# Sense_LDC1612.net
KiCad netlist of a schematic drawn in Altium Designer
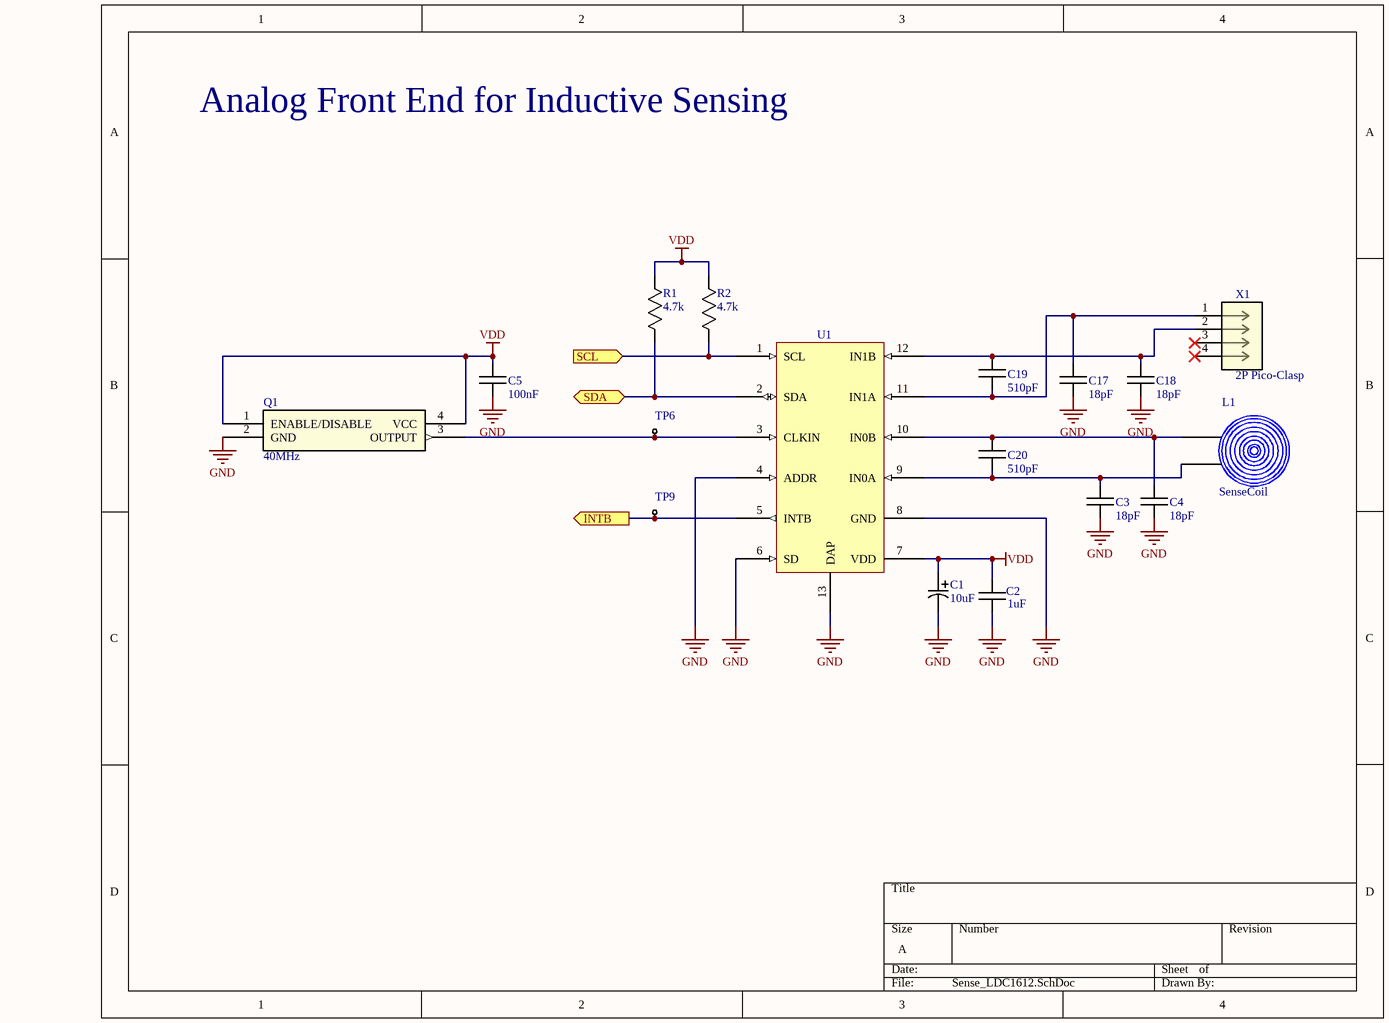
[diagram p0: Sense_LDC1612.SchDoc]

(export (version "E")
  (design (tool "Eeschema 10.0.6"))
  (components
    (comp (ref "C1")
      (value "10uF")
      (footprint "CAP1206_TAJA")
      (description "Cap Tant Solid 10uF 16V A CASE 10%( 3.2 X 1.6 X 1.6mm) Inward L SMD 3216-18 3 Ohm 125C T/R")
      (fields
        (field (name "MANUFACTURER_PART_NUMBER") "TAJA106K016RNJ")
        (field (name "MANUFACTURER") "Kyocera AVX")
        (field (name "COPYRIGHT") "Copyright (C) 2023 Ultra Librarian. All rights reserved.")
      )
      (libsource (lib "Schlib1") (part "TAJA106K016RNJ"))
    )
    (comp (ref "C2")
      (value "1uF")
      (footprint "CAP0805")
      (description "Multilayer Ceramic Capacitor, 1 uF, 50 V, ± 10%, X7R, 0805 [2012 Metric]")
      (fields
        (field (name "MANUFACTURER") "Samsung")
        (field (name "MANUFACTURER PART NUMBER") "CL21B105KBFNNNE")
      )
      (libsource (lib "Schlib1") (part "CL21B105KBFNNNE"))
    )
    (comp (ref "C3")
      (value "18pF")
      (footprint "CAP0805")
      (description "0805 18 pF 50 V ±5 % Tolerance C0G/NP0 SMT Multilayer Ceramic Chip Capacitor")
      (fields
        (field (name "MANUFACTURER") "Vishay")
        (field (name "MANUFACTURER PART NUMBER") "VJ0805A180JXACW1BC")
      )
      (libsource (lib "Schlib1") (part "VJ0805A180JXACW1BC"))
    )
    (comp (ref "C4")
      (value "18pF")
      (footprint "CAP0805")
      (description "0805 18 pF 50 V ±5 % Tolerance C0G/NP0 SMT Multilayer Ceramic Chip Capacitor")
      (fields
        (field (name "MANUFACTURER") "Vishay")
        (field (name "MANUFACTURER PART NUMBER") "VJ0805A180JXACW1BC")
      )
      (libsource (lib "Schlib1") (part "VJ0805A180JXACW1BC"))
    )
    (comp (ref "C5")
      (value "100nF")
      (footprint "CAP0805")
      (description "Multilayer Ceramic Capacitor, 0.1 uF, 50 V, ± 10%, X7R, 0805 [2012 Metric]")
      (fields
        (field (name "MANUFACTURER") "Yageo")
        (field (name "MANUFACTURER PART NUMBER") "CC0805KRX7R9BB104")
      )
      (libsource (lib "Schlib1") (part "CC0805KRX7R9BB104"))
    )
    (comp (ref "C17")
      (value "18pF")
      (footprint "CAP0805")
      (description "0805 18 pF 50 V ±5 % Tolerance C0G/NP0 SMT Multilayer Ceramic Chip Capacitor")
      (fields
        (field (name "MANUFACTURER") "Vishay")
        (field (name "MANUFACTURER PART NUMBER") "VJ0805A180JXACW1BC")
      )
      (libsource (lib "Schlib1") (part "VJ0805A180JXACW1BC"))
    )
    (comp (ref "C18")
      (value "18pF")
      (footprint "CAP0805")
      (description "0805 18 pF 50 V ±5 % Tolerance C0G/NP0 SMT Multilayer Ceramic Chip Capacitor")
      (fields
        (field (name "MANUFACTURER") "Vishay")
        (field (name "MANUFACTURER PART NUMBER") "VJ0805A180JXACW1BC")
      )
      (libsource (lib "Schlib1") (part "VJ0805A180JXACW1BC"))
    )
    (comp (ref "C19")
      (value "510pF")
      (footprint "CAP0805")
      (description "0805 510 pF 50 V ±5 % Tolerance NP0 SMT Multilayer Ceramic Capacitor")
      (fields
        (field (name "MANUFACTURER") "Yageo")
        (field (name "MANUFACTURER PART NUMBER") "CC0805JRNPO9BN511")
      )
      (libsource (lib "Schlib1") (part "CC0805JRNPO9BN511"))
    )
    (comp (ref "C20")
      (value "510pF")
      (footprint "CAP0805")
      (description "0805 510 pF 50 V ±5 % Tolerance NP0 SMT Multilayer Ceramic Capacitor")
      (fields
        (field (name "MANUFACTURER") "Yageo")
        (field (name "MANUFACTURER PART NUMBER") "CC0805JRNPO9BN511")
      )
      (libsource (lib "Schlib1") (part "CC0805JRNPO9BN511"))
    )
    (comp (ref "L1") (value "SenseCoil") (footprint "Coil_4L") (libsource (lib "Schlib1") (part "SenseCoil")))
    (comp (ref "Q1")
      (value "40MHz")
      (footprint "KC2520Z_KYO")
      (description "Xtal Osc Xo 40.0000MHZ Cmos SMD")
      (fields
        (field (name "MANUFACTURER") "Kyocera AVX")
        (field (name "MANUFACTURER PART NUMBER") "KC2520Z40.0000C15XXK")
      )
      (libsource (lib "Schlib1") (part "KC2520Z40.0000C15XXK"))
    )
    (comp (ref "R1")
      (value "4.7k")
      (footprint "RES0805")
      (description "Res Thick Film 0805 4.7K Ohm 5% 1/8W ±200ppm/°C Molded SMD Punched Carrier T/R")
      (fields
        (field (name "MANUFACTURER") "Panasonic")
        (field (name "MANUFACTURER PART NUMBER") "ERJ-6GEYJ472V")
      )
      (libsource (lib "Schlib1") (part "ERJ-6GEYJ472V"))
    )
    (comp (ref "R2")
      (value "4.7k")
      (footprint "RES0805")
      (description "Res Thick Film 0805 4.7K Ohm 5% 1/8W ±200ppm/°C Molded SMD Punched Carrier T/R")
      (fields
        (field (name "MANUFACTURER") "Panasonic")
        (field (name "MANUFACTURER PART NUMBER") "ERJ-6GEYJ472V")
      )
      (libsource (lib "Schlib1") (part "ERJ-6GEYJ472V"))
    )
    (comp (ref "TP6")
      (value "1mm Test Point")
      (footprint "TP_1MM")
      (libsource (lib "Schlib1") (part "TestPoint_1mm"))
    )
    (comp (ref "TP9")
      (value "1mm Test Point")
      (footprint "TP_1MM")
      (libsource (lib "Schlib1") (part "TestPoint_1mm"))
    )
    (comp (ref "U1")
      (value "Inductive Sensor 2Ch")
      (footprint "LDC1612")
      (description "2-Ch, 28-bit, high-resolution Inductance to digital converter 12-WSON -40 to 125")
      (fields
        (field (name "MANUFACTURER") "Texas Instruments")
        (field (name "MANUFACTURER PART NUMBER") "LDC1612DNTR")
      )
      (libsource (lib "Schlib1") (part "LDC1612"))
    )
    (comp (ref "X1")
      (value "2P Pico-Clasp")
      (footprint "CON_2023960207")
      (description "Conn Shrouded Header (4 Sides) HDR 2 POS 1mm Solder RA Side Entry SMD Pico-Clasp™ T/R")
      (fields (field (name "MANUFACTURER") "Molex") (field (name "MANUFACTURER PART NUMBER") "202396-0207"))
      (libsource (lib "Schlib1") (part "202396-0207"))
    )
  )
  (nets
    (net (code "1") (name "/INTB") (class "Default")
      (node (ref "TP9") (pin "1") (pinfunction "0_1") (pintype "passive"))
      (node (ref "U1") (pin "5") (pinfunction "INTB_5") (pintype "output"))
    )
    (net (code "2") (name "/SCL") (class "Default")
      (node (ref "R2") (pin "2") (pinfunction "2_2") (pintype "passive"))
      (node (ref "U1") (pin "1") (pinfunction "SCL_1") (pintype "input"))
    )
    (net (code "3") (name "/SDA") (class "Default")
      (node (ref "R1") (pin "2") (pinfunction "2_2") (pintype "passive"))
      (node (ref "U1") (pin "2") (pinfunction "SDA_2") (pintype "bidirectional"))
    )
    (net (code "4") (name "GND") (class "Default")
      (node (ref "C1") (pin "2") (pinfunction "2_2") (pintype "passive"))
      (node (ref "C17") (pin "2") (pinfunction "2_2") (pintype "passive"))
      (node (ref "C18") (pin "2") (pinfunction "2_2") (pintype "passive"))
      (node (ref "C2") (pin "2") (pinfunction "2_2") (pintype "passive"))
      (node (ref "C3") (pin "2") (pinfunction "2_2") (pintype "passive"))
      (node (ref "C4") (pin "2") (pinfunction "2_2") (pintype "passive"))
      (node (ref "C5") (pin "2") (pinfunction "2_2") (pintype "passive"))
      (node (ref "Q1") (pin "2") (pinfunction "GND_2") (pintype "power_in"))
      (node (ref "U1") (pin "13") (pinfunction "DAP_13") (pintype "passive"))
      (node (ref "U1") (pin "4") (pinfunction "ADDR_4") (pintype "input"))
      (node (ref "U1") (pin "6") (pinfunction "SD_6") (pintype "input"))
      (node (ref "U1") (pin "8") (pinfunction "GND_8") (pintype "power_in"))
    )
    (net (code "5") (name "Net-(Q1-OUTPUT)") (class "Default")
      (node (ref "Q1") (pin "3") (pinfunction "OUTPUT_3") (pintype "output"))
      (node (ref "TP6") (pin "1") (pinfunction "0_1") (pintype "passive"))
      (node (ref "U1") (pin "3") (pinfunction "CLKIN_3") (pintype "input"))
    )
    (net (code "6") (name "Net-(U1-IN0A)") (class "Default")
      (node (ref "C20") (pin "1") (pinfunction "1_1") (pintype "passive"))
      (node (ref "C3") (pin "1") (pinfunction "1_1") (pintype "passive"))
      (node (ref "L1") (pin "1") (pinfunction "1_1") (pintype "passive"))
      (node (ref "U1") (pin "9") (pinfunction "IN0A_9") (pintype "input"))
    )
    (net (code "7") (name "Net-(U1-IN0B)") (class "Default")
      (node (ref "C20") (pin "2") (pinfunction "2_2") (pintype "passive"))
      (node (ref "C4") (pin "1") (pinfunction "1_1") (pintype "passive"))
      (node (ref "L1") (pin "1") (pinfunction "1_1") (pintype "passive"))
      (node (ref "U1") (pin "10") (pinfunction "IN0B_10") (pintype "input"))
    )
    (net (code "8") (name "Net-(U1-IN1A)") (class "Default")
      (node (ref "C17") (pin "1") (pinfunction "1_1") (pintype "passive"))
      (node (ref "C19") (pin "1") (pinfunction "1_1") (pintype "passive"))
      (node (ref "U1") (pin "11") (pinfunction "IN1A_11") (pintype "input"))
      (node (ref "X1") (pin "1") (pinfunction "1_1") (pintype "passive"))
    )
    (net (code "9") (name "Net-(U1-IN1B)") (class "Default")
      (node (ref "C18") (pin "1") (pinfunction "1_1") (pintype "passive"))
      (node (ref "C19") (pin "2") (pinfunction "2_2") (pintype "passive"))
      (node (ref "U1") (pin "12") (pinfunction "IN1B_12") (pintype "input"))
      (node (ref "X1") (pin "2") (pinfunction "2_2") (pintype "passive"))
    )
    (net (code "10") (name "VDD") (class "Default")
      (node (ref "C1") (pin "1") (pinfunction "1_1") (pintype "passive"))
      (node (ref "C2") (pin "1") (pinfunction "1_1") (pintype "passive"))
      (node (ref "C5") (pin "1") (pinfunction "1_1") (pintype "passive"))
      (node (ref "Q1") (pin "1") (pinfunction "ENABLE/DISABLE_1") (pintype "passive"))
      (node (ref "Q1") (pin "4") (pinfunction "VCC_4") (pintype "power_in"))
      (node (ref "R1") (pin "1") (pinfunction "1_1") (pintype "passive"))
      (node (ref "R2") (pin "1") (pinfunction "1_1") (pintype "passive"))
      (node (ref "U1") (pin "7") (pinfunction "VDD_7") (pintype "power_in"))
    )
    (net (code "11") (name "unconnected-(X1-Pad3)") (class "Default")
      (node (ref "X1") (pin "3") (pinfunction "3_3") (pintype "passive+no_connect"))
    )
    (net (code "12") (name "unconnected-(X1-Pad4)") (class "Default")
      (node (ref "X1") (pin "4") (pinfunction "4_4") (pintype "passive+no_connect"))
    )
  )
)
